# Motor_Driver.net
KiCad netlist of a schematic drawn in Altium Designer
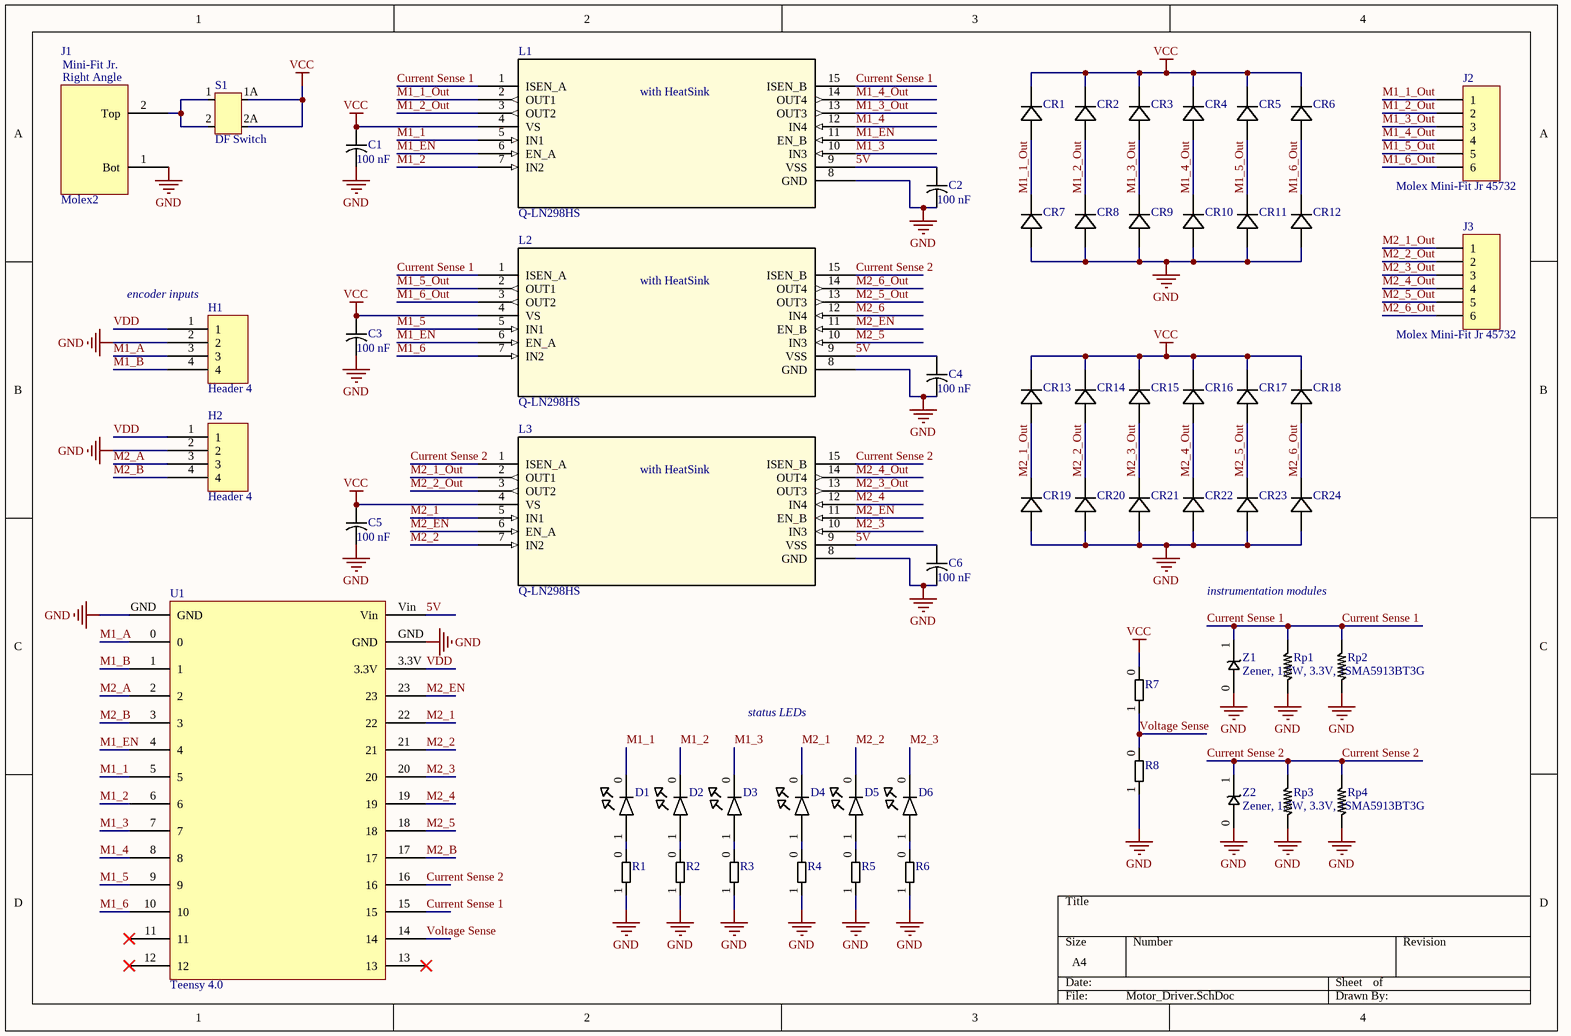
[diagram p0: Motor_Driver.SchDoc]

(export (version "E")
  (design (tool "Eeschema 10.0.6"))
  (components
    (comp (ref "C1")
      (value "100 nF")
      (footprint "CC0805N-M")
      (description "No Description Available")
      (fields
        (field (name "MANUFACTURER_PART_NUMBER") "C0805C104M5RACTU")
        (field (name "COPYRIGHT") "Copyright (C) 2018 Accelerated Designs. All rights reserved")
      )
      (libsource (lib "Motor_Driver") (part "C0805C104M5RACTU"))
    )
    (comp (ref "C2")
      (value "100 nF")
      (footprint "CC0805N-M")
      (description "No Description Available")
      (fields
        (field (name "MANUFACTURER_PART_NUMBER") "C0805C104M5RACTU")
        (field (name "COPYRIGHT") "Copyright (C) 2018 Accelerated Designs. All rights reserved")
      )
      (libsource (lib "Motor_Driver") (part "C0805C104M5RACTU"))
    )
    (comp (ref "C3")
      (value "100 nF")
      (footprint "CC0805N-M")
      (description "No Description Available")
      (fields
        (field (name "MANUFACTURER_PART_NUMBER") "C0805C104M5RACTU")
        (field (name "COPYRIGHT") "Copyright (C) 2018 Accelerated Designs. All rights reserved")
      )
      (libsource (lib "Motor_Driver") (part "C0805C104M5RACTU"))
    )
    (comp (ref "C4")
      (value "100 nF")
      (footprint "CC0805N-M")
      (description "No Description Available")
      (fields
        (field (name "MANUFACTURER_PART_NUMBER") "C0805C104M5RACTU")
        (field (name "COPYRIGHT") "Copyright (C) 2018 Accelerated Designs. All rights reserved")
      )
      (libsource (lib "Motor_Driver") (part "C0805C104M5RACTU"))
    )
    (comp (ref "C5")
      (value "100 nF")
      (footprint "CC0805N-M")
      (description "No Description Available")
      (fields
        (field (name "MANUFACTURER_PART_NUMBER") "C0805C104M5RACTU")
        (field (name "COPYRIGHT") "Copyright (C) 2018 Accelerated Designs. All rights reserved")
      )
      (libsource (lib "Motor_Driver") (part "C0805C104M5RACTU"))
    )
    (comp (ref "C6")
      (value "100 nF")
      (footprint "CC0805N-M")
      (description "No Description Available")
      (fields
        (field (name "MANUFACTURER_PART_NUMBER") "C0805C104M5RACTU")
        (field (name "COPYRIGHT") "Copyright (C) 2018 Accelerated Designs. All rights reserved")
      )
      (libsource (lib "Motor_Driver") (part "C0805C104M5RACTU"))
    )
    (comp (ref "CR1")
      (value "Part Number: SD1206S040S2R0")
      (footprint "SD1206")
      (fields
        (field (name "MANUFACTURER_PART_NUMBER") "SD1206S040S2R0")
        (field (name "COPYRIGHT") "Copyright (C) 2018 Accelerated Designs. All rights reserved")
      )
      (libsource (lib "Motor_Driver") (part "SD1206S040S2R0"))
    )
    (comp (ref "CR2")
      (value "Part Number: SD1206S040S2R0")
      (footprint "SD1206")
      (fields
        (field (name "MANUFACTURER_PART_NUMBER") "SD1206S040S2R0")
        (field (name "COPYRIGHT") "Copyright (C) 2018 Accelerated Designs. All rights reserved")
      )
      (libsource (lib "Motor_Driver") (part "SD1206S040S2R0"))
    )
    (comp (ref "CR3")
      (value "Part Number: SD1206S040S2R0")
      (footprint "SD1206")
      (fields
        (field (name "MANUFACTURER_PART_NUMBER") "SD1206S040S2R0")
        (field (name "COPYRIGHT") "Copyright (C) 2018 Accelerated Designs. All rights reserved")
      )
      (libsource (lib "Motor_Driver") (part "SD1206S040S2R0"))
    )
    (comp (ref "CR4")
      (value "Part Number: SD1206S040S2R0")
      (footprint "SD1206")
      (fields
        (field (name "MANUFACTURER_PART_NUMBER") "SD1206S040S2R0")
        (field (name "COPYRIGHT") "Copyright (C) 2018 Accelerated Designs. All rights reserved")
      )
      (libsource (lib "Motor_Driver") (part "SD1206S040S2R0"))
    )
    (comp (ref "CR5")
      (value "Part Number: SD1206S040S2R0")
      (footprint "SD1206")
      (fields
        (field (name "MANUFACTURER_PART_NUMBER") "SD1206S040S2R0")
        (field (name "COPYRIGHT") "Copyright (C) 2018 Accelerated Designs. All rights reserved")
      )
      (libsource (lib "Motor_Driver") (part "SD1206S040S2R0"))
    )
    (comp (ref "CR6")
      (value "Part Number: SD1206S040S2R0")
      (footprint "SD1206")
      (fields
        (field (name "MANUFACTURER_PART_NUMBER") "SD1206S040S2R0")
        (field (name "COPYRIGHT") "Copyright (C) 2018 Accelerated Designs. All rights reserved")
      )
      (libsource (lib "Motor_Driver") (part "SD1206S040S2R0"))
    )
    (comp (ref "CR7")
      (value "Part Number: SD1206S040S2R0")
      (footprint "SD1206")
      (fields
        (field (name "MANUFACTURER_PART_NUMBER") "SD1206S040S2R0")
        (field (name "COPYRIGHT") "Copyright (C) 2018 Accelerated Designs. All rights reserved")
      )
      (libsource (lib "Motor_Driver") (part "SD1206S040S2R0"))
    )
    (comp (ref "CR8")
      (value "Part Number: SD1206S040S2R0")
      (footprint "SD1206")
      (fields
        (field (name "MANUFACTURER_PART_NUMBER") "SD1206S040S2R0")
        (field (name "COPYRIGHT") "Copyright (C) 2018 Accelerated Designs. All rights reserved")
      )
      (libsource (lib "Motor_Driver") (part "SD1206S040S2R0"))
    )
    (comp (ref "CR9")
      (value "Part Number: SD1206S040S2R0")
      (footprint "SD1206")
      (fields
        (field (name "MANUFACTURER_PART_NUMBER") "SD1206S040S2R0")
        (field (name "COPYRIGHT") "Copyright (C) 2018 Accelerated Designs. All rights reserved")
      )
      (libsource (lib "Motor_Driver") (part "SD1206S040S2R0"))
    )
    (comp (ref "CR10")
      (value "Part Number: SD1206S040S2R0")
      (footprint "SD1206")
      (fields
        (field (name "MANUFACTURER_PART_NUMBER") "SD1206S040S2R0")
        (field (name "COPYRIGHT") "Copyright (C) 2018 Accelerated Designs. All rights reserved")
      )
      (libsource (lib "Motor_Driver") (part "SD1206S040S2R0"))
    )
    (comp (ref "CR11")
      (value "Part Number: SD1206S040S2R0")
      (footprint "SD1206")
      (fields
        (field (name "MANUFACTURER_PART_NUMBER") "SD1206S040S2R0")
        (field (name "COPYRIGHT") "Copyright (C) 2018 Accelerated Designs. All rights reserved")
      )
      (libsource (lib "Motor_Driver") (part "SD1206S040S2R0"))
    )
    (comp (ref "CR12")
      (value "Part Number: SD1206S040S2R0")
      (footprint "SD1206")
      (fields
        (field (name "MANUFACTURER_PART_NUMBER") "SD1206S040S2R0")
        (field (name "COPYRIGHT") "Copyright (C) 2018 Accelerated Designs. All rights reserved")
      )
      (libsource (lib "Motor_Driver") (part "SD1206S040S2R0"))
    )
    (comp (ref "CR13")
      (value "Part Number: SD1206S040S2R0")
      (footprint "SD1206")
      (fields
        (field (name "MANUFACTURER_PART_NUMBER") "SD1206S040S2R0")
        (field (name "COPYRIGHT") "Copyright (C) 2018 Accelerated Designs. All rights reserved")
      )
      (libsource (lib "Motor_Driver") (part "SD1206S040S2R0"))
    )
    (comp (ref "CR14")
      (value "Part Number: SD1206S040S2R0")
      (footprint "SD1206")
      (fields
        (field (name "MANUFACTURER_PART_NUMBER") "SD1206S040S2R0")
        (field (name "COPYRIGHT") "Copyright (C) 2018 Accelerated Designs. All rights reserved")
      )
      (libsource (lib "Motor_Driver") (part "SD1206S040S2R0"))
    )
    (comp (ref "CR15")
      (value "Part Number: SD1206S040S2R0")
      (footprint "SD1206")
      (fields
        (field (name "MANUFACTURER_PART_NUMBER") "SD1206S040S2R0")
        (field (name "COPYRIGHT") "Copyright (C) 2018 Accelerated Designs. All rights reserved")
      )
      (libsource (lib "Motor_Driver") (part "SD1206S040S2R0"))
    )
    (comp (ref "CR16")
      (value "Part Number: SD1206S040S2R0")
      (footprint "SD1206")
      (fields
        (field (name "MANUFACTURER_PART_NUMBER") "SD1206S040S2R0")
        (field (name "COPYRIGHT") "Copyright (C) 2018 Accelerated Designs. All rights reserved")
      )
      (libsource (lib "Motor_Driver") (part "SD1206S040S2R0"))
    )
    (comp (ref "CR17")
      (value "Part Number: SD1206S040S2R0")
      (footprint "SD1206")
      (fields
        (field (name "MANUFACTURER_PART_NUMBER") "SD1206S040S2R0")
        (field (name "COPYRIGHT") "Copyright (C) 2018 Accelerated Designs. All rights reserved")
      )
      (libsource (lib "Motor_Driver") (part "SD1206S040S2R0"))
    )
    (comp (ref "CR18")
      (value "Part Number: SD1206S040S2R0")
      (footprint "SD1206")
      (fields
        (field (name "MANUFACTURER_PART_NUMBER") "SD1206S040S2R0")
        (field (name "COPYRIGHT") "Copyright (C) 2018 Accelerated Designs. All rights reserved")
      )
      (libsource (lib "Motor_Driver") (part "SD1206S040S2R0"))
    )
    (comp (ref "CR19")
      (value "Part Number: SD1206S040S2R0")
      (footprint "SD1206")
      (fields
        (field (name "MANUFACTURER_PART_NUMBER") "SD1206S040S2R0")
        (field (name "COPYRIGHT") "Copyright (C) 2018 Accelerated Designs. All rights reserved")
      )
      (libsource (lib "Motor_Driver") (part "SD1206S040S2R0"))
    )
    (comp (ref "CR20")
      (value "Part Number: SD1206S040S2R0")
      (footprint "SD1206")
      (fields
        (field (name "MANUFACTURER_PART_NUMBER") "SD1206S040S2R0")
        (field (name "COPYRIGHT") "Copyright (C) 2018 Accelerated Designs. All rights reserved")
      )
      (libsource (lib "Motor_Driver") (part "SD1206S040S2R0"))
    )
    (comp (ref "CR21")
      (value "Part Number: SD1206S040S2R0")
      (footprint "SD1206")
      (fields
        (field (name "MANUFACTURER_PART_NUMBER") "SD1206S040S2R0")
        (field (name "COPYRIGHT") "Copyright (C) 2018 Accelerated Designs. All rights reserved")
      )
      (libsource (lib "Motor_Driver") (part "SD1206S040S2R0"))
    )
    (comp (ref "CR22")
      (value "Part Number: SD1206S040S2R0")
      (footprint "SD1206")
      (fields
        (field (name "MANUFACTURER_PART_NUMBER") "SD1206S040S2R0")
        (field (name "COPYRIGHT") "Copyright (C) 2018 Accelerated Designs. All rights reserved")
      )
      (libsource (lib "Motor_Driver") (part "SD1206S040S2R0"))
    )
    (comp (ref "CR23")
      (value "Part Number: SD1206S040S2R0")
      (footprint "SD1206")
      (fields
        (field (name "MANUFACTURER_PART_NUMBER") "SD1206S040S2R0")
        (field (name "COPYRIGHT") "Copyright (C) 2018 Accelerated Designs. All rights reserved")
      )
      (libsource (lib "Motor_Driver") (part "SD1206S040S2R0"))
    )
    (comp (ref "CR24")
      (value "Part Number: SD1206S040S2R0")
      (footprint "SD1206")
      (fields
        (field (name "MANUFACTURER_PART_NUMBER") "SD1206S040S2R0")
        (field (name "COPYRIGHT") "Copyright (C) 2018 Accelerated Designs. All rights reserved")
      )
      (libsource (lib "Motor_Driver") (part "SD1206S040S2R0"))
    )
    (comp (ref "D1")
      (value "Test LED")
      (footprint "Test LED")
      (libsource (lib "Motor_Driver") (part "Test LED"))
    )
    (comp (ref "D2")
      (value "Test LED")
      (footprint "Test LED")
      (libsource (lib "Motor_Driver") (part "Test LED"))
    )
    (comp (ref "D3")
      (value "Test LED")
      (footprint "Test LED")
      (libsource (lib "Motor_Driver") (part "Test LED"))
    )
    (comp (ref "D4")
      (value "Test LED")
      (footprint "Test LED")
      (libsource (lib "Motor_Driver") (part "Test LED"))
    )
    (comp (ref "D5")
      (value "Test LED")
      (footprint "Test LED")
      (libsource (lib "Motor_Driver") (part "Test LED"))
    )
    (comp (ref "D6")
      (value "Test LED")
      (footprint "Test LED")
      (libsource (lib "Motor_Driver") (part "Test LED"))
    )
    (comp (ref "H1")
      (value "Header 4")
      (footprint "4 Header")
      (libsource (lib "Motor_Driver") (part "Header 4"))
    )
    (comp (ref "H2")
      (value "Header 4")
      (footprint "4 Header")
      (libsource (lib "Motor_Driver") (part "Header 4"))
    )
    (comp (ref "J1")
      (value "Molex2")
      (footprint "MOLEX MINI2")
      (libsource (lib "Motor_Driver") (part "Molex2"))
    )
    (comp (ref "J2")
      (value "Molex Mini-Fit Jr 45732")
      (footprint "Molex Mini-Fit Jr")
      (description "Molex CONN HEADER R/A 6POS 4.2MM")
      (libsource (lib "Motor_Driver") (part "Molex 0457320001"))
    )
    (comp (ref "J3")
      (value "Molex Mini-Fit Jr 45732")
      (footprint "Molex Mini-Fit Jr")
      (description "Molex CONN HEADER R/A 6POS 4.2MM")
      (libsource (lib "Motor_Driver") (part "Molex 0457320001"))
    )
    (comp (ref "L1")
      (value "Q-LN298HS")
      (footprint "Multiwatt15_V_ELEC391HS")
      (description "LN298 - IC Bridge Driver Par 15Multiwatt")
      (fields
        (field (name "MANUFACTURER_PART_NUMBER") "L298N")
        (field (name "COPYRIGHT") "Copyright (C) 2015 Accelerated Designs. All rights reserved")
      )
      (libsource (lib "Additional Parts 391") (part "Q-LN298HS"))
    )
    (comp (ref "L2")
      (value "Q-LN298HS")
      (footprint "Multiwatt15_V_ELEC391HS")
      (description "LN298 - IC Bridge Driver Par 15Multiwatt")
      (fields
        (field (name "MANUFACTURER_PART_NUMBER") "L298N")
        (field (name "COPYRIGHT") "Copyright (C) 2015 Accelerated Designs. All rights reserved")
      )
      (libsource (lib "Additional Parts 391") (part "Q-LN298HS"))
    )
    (comp (ref "L3")
      (value "Q-LN298HS")
      (footprint "Multiwatt15_V_ELEC391HS")
      (description "LN298 - IC Bridge Driver Par 15Multiwatt")
      (fields
        (field (name "MANUFACTURER_PART_NUMBER") "L298N")
        (field (name "COPYRIGHT") "Copyright (C) 2015 Accelerated Designs. All rights reserved")
      )
      (libsource (lib "Additional Parts 391") (part "Q-LN298HS"))
    )
    (comp (ref "R1") (value "StdRes") (footprint "StdRes") (libsource (lib "Motor_Driver") (part "StdRes")))
    (comp (ref "R2") (value "StdRes") (footprint "StdRes") (libsource (lib "Motor_Driver") (part "StdRes")))
    (comp (ref "R3") (value "StdRes") (footprint "StdRes") (libsource (lib "Motor_Driver") (part "StdRes")))
    (comp (ref "R4") (value "StdRes") (footprint "StdRes") (libsource (lib "Motor_Driver") (part "StdRes")))
    (comp (ref "R5") (value "StdRes") (footprint "StdRes") (libsource (lib "Motor_Driver") (part "StdRes")))
    (comp (ref "R6") (value "StdRes") (footprint "StdRes") (libsource (lib "Motor_Driver") (part "StdRes")))
    (comp (ref "R7") (value "StdRes") (footprint "StdRes") (libsource (lib "Motor_Driver") (part "StdRes")))
    (comp (ref "R8") (value "StdRes") (footprint "StdRes") (libsource (lib "Motor_Driver") (part "StdRes")))
    (comp (ref "Rp1")
      (value "SQP500 Power Resistor")
      (footprint "SQP500 Power Resistor")
      (libsource (lib "Motor_Driver") (part "SQP500 Power Resistor"))
    )
    (comp (ref "Rp2")
      (value "SQP500 Power Resistor")
      (footprint "SQP500 Power Resistor")
      (libsource (lib "Motor_Driver") (part "SQP500 Power Resistor"))
    )
    (comp (ref "Rp3")
      (value "SQP500 Power Resistor")
      (footprint "SQP500 Power Resistor")
      (libsource (lib "Motor_Driver") (part "SQP500 Power Resistor"))
    )
    (comp (ref "Rp4")
      (value "SQP500 Power Resistor")
      (footprint "SQP500 Power Resistor")
      (libsource (lib "Motor_Driver") (part "SQP500 Power Resistor"))
    )
    (comp (ref "S1")
      (value "DF Switch")
      (footprint "DF Switch")
      (libsource (lib "Motor_Driver") (part "DF Switch"))
    )
    (comp (ref "U1")
      (value "Teensy 4.0")
      (footprint "Teensy 4.0")
      (libsource (lib "Motor_Driver") (part "Teensy 4.0"))
    )
    (comp (ref "Z1")
      (value "Zener, 1.5W, 3.3V, 1SMA5913BT3G")
      (footprint "Zener, 1.5W, 3.3V, 1SMA5913BT3G")
      (libsource (lib "Motor_Driver") (part "Zener, 1.5W, 3.3V, 1SMA5913BT3G"))
    )
    (comp (ref "Z2")
      (value "Zener, 1.5W, 3.3V, 1SMA5913BT3G")
      (footprint "Zener, 1.5W, 3.3V, 1SMA5913BT3G")
      (libsource (lib "Motor_Driver") (part "Zener, 1.5W, 3.3V, 1SMA5913BT3G"))
    )
  )
  (nets
    (net (code "1") (name "/5V") (class "Default")
      (node (ref "C2") (pin "1") (pinfunction "1_1") (pintype "passive"))
      (node (ref "C4") (pin "1") (pinfunction "1_1") (pintype "passive"))
      (node (ref "C6") (pin "1") (pinfunction "1_1") (pintype "passive"))
      (node (ref "L1") (pin "9") (pinfunction "VSS_9") (pintype "power_in"))
      (node (ref "L2") (pin "9") (pinfunction "VSS_9") (pintype "power_in"))
      (node (ref "L3") (pin "9") (pinfunction "VSS_9") (pintype "power_in"))
      (node (ref "U1") (pin "Vin") (pinfunction "Vin_Vin") (pintype "passive"))
    )
    (net (code "2") (name "/Current Sense 1") (class "Default")
      (node (ref "L1") (pin "1") (pinfunction "ISEN_A_1") (pintype "passive"))
      (node (ref "L1") (pin "15") (pinfunction "ISEN_B_15") (pintype "passive"))
      (node (ref "L2") (pin "1") (pinfunction "ISEN_A_1") (pintype "passive"))
      (node (ref "Rp1") (pin "1") (pintype "passive"))
      (node (ref "Rp2") (pin "1") (pintype "passive"))
      (node (ref "U1") (pin "15") (pinfunction "15_15") (pintype "passive"))
      (node (ref "Z1") (pin "1") (pinfunction "1_1") (pintype "passive"))
    )
    (net (code "3") (name "/Current Sense 2") (class "Default")
      (node (ref "L2") (pin "15") (pinfunction "ISEN_B_15") (pintype "passive"))
      (node (ref "L3") (pin "1") (pinfunction "ISEN_A_1") (pintype "passive"))
      (node (ref "L3") (pin "15") (pinfunction "ISEN_B_15") (pintype "passive"))
      (node (ref "Rp3") (pin "1") (pintype "passive"))
      (node (ref "Rp4") (pin "1") (pintype "passive"))
      (node (ref "U1") (pin "16") (pinfunction "16_16") (pintype "passive"))
      (node (ref "Z2") (pin "1") (pinfunction "1_1") (pintype "passive"))
    )
    (net (code "4") (name "/M1_1") (class "Default")
      (node (ref "D1") (pin "0") (pinfunction "0_0") (pintype "passive"))
      (node (ref "L1") (pin "5") (pinfunction "IN1_5") (pintype "input"))
      (node (ref "U1") (pin "5") (pinfunction "5_5") (pintype "passive"))
    )
    (net (code "5") (name "/M1_1_Out") (class "Default")
      (node (ref "CR1") (pin "2") (pinfunction "2_2") (pintype "passive"))
      (node (ref "CR7") (pin "1") (pinfunction "1_1") (pintype "passive"))
      (node (ref "J2") (pin "1") (pinfunction "1_1") (pintype "power_in"))
      (node (ref "L1") (pin "2") (pinfunction "OUT1_2") (pintype "output"))
    )
    (net (code "6") (name "/M1_2") (class "Default")
      (node (ref "D2") (pin "0") (pinfunction "0_0") (pintype "passive"))
      (node (ref "L1") (pin "7") (pinfunction "IN2_7") (pintype "input"))
      (node (ref "U1") (pin "6") (pinfunction "6_6") (pintype "passive"))
    )
    (net (code "7") (name "/M1_2_Out") (class "Default")
      (node (ref "CR2") (pin "2") (pinfunction "2_2") (pintype "passive"))
      (node (ref "CR8") (pin "1") (pinfunction "1_1") (pintype "passive"))
      (node (ref "J2") (pin "2") (pinfunction "2_2") (pintype "power_in"))
      (node (ref "L1") (pin "3") (pinfunction "OUT2_3") (pintype "output"))
    )
    (net (code "8") (name "/M1_3") (class "Default")
      (node (ref "D3") (pin "0") (pinfunction "0_0") (pintype "passive"))
      (node (ref "L1") (pin "10") (pinfunction "IN3_10") (pintype "input"))
      (node (ref "U1") (pin "7") (pinfunction "7_7") (pintype "passive"))
    )
    (net (code "9") (name "/M1_3_Out") (class "Default")
      (node (ref "CR3") (pin "2") (pinfunction "2_2") (pintype "passive"))
      (node (ref "CR9") (pin "1") (pinfunction "1_1") (pintype "passive"))
      (node (ref "J2") (pin "3") (pinfunction "3_3") (pintype "power_in"))
      (node (ref "L1") (pin "13") (pinfunction "OUT3_13") (pintype "output"))
    )
    (net (code "10") (name "/M1_4") (class "Default")
      (node (ref "L1") (pin "12") (pinfunction "IN4_12") (pintype "input"))
      (node (ref "U1") (pin "8") (pinfunction "8_8") (pintype "passive"))
    )
    (net (code "11") (name "/M1_4_Out") (class "Default")
      (node (ref "CR10") (pin "1") (pinfunction "1_1") (pintype "passive"))
      (node (ref "CR4") (pin "2") (pinfunction "2_2") (pintype "passive"))
      (node (ref "J2") (pin "4") (pinfunction "4_4") (pintype "power_in"))
      (node (ref "L1") (pin "14") (pinfunction "OUT4_14") (pintype "output"))
    )
    (net (code "12") (name "/M1_5") (class "Default")
      (node (ref "L2") (pin "5") (pinfunction "IN1_5") (pintype "input"))
      (node (ref "U1") (pin "9") (pinfunction "9_9") (pintype "passive"))
    )
    (net (code "13") (name "/M1_5_Out") (class "Default")
      (node (ref "CR11") (pin "1") (pinfunction "1_1") (pintype "passive"))
      (node (ref "CR5") (pin "2") (pinfunction "2_2") (pintype "passive"))
      (node (ref "J2") (pin "5") (pinfunction "5_5") (pintype "power_in"))
      (node (ref "L2") (pin "2") (pinfunction "OUT1_2") (pintype "output"))
    )
    (net (code "14") (name "/M1_6") (class "Default")
      (node (ref "L2") (pin "7") (pinfunction "IN2_7") (pintype "input"))
      (node (ref "U1") (pin "10") (pinfunction "10_10") (pintype "passive"))
    )
    (net (code "15") (name "/M1_6_Out") (class "Default")
      (node (ref "CR12") (pin "1") (pinfunction "1_1") (pintype "passive"))
      (node (ref "CR6") (pin "2") (pinfunction "2_2") (pintype "passive"))
      (node (ref "J2") (pin "6") (pinfunction "6_6") (pintype "power_in"))
      (node (ref "L2") (pin "3") (pinfunction "OUT2_3") (pintype "output"))
    )
    (net (code "16") (name "/M1_A") (class "Default")
      (node (ref "H1") (pin "3") (pinfunction "3_3") (pintype "passive"))
      (node (ref "U1") (pin "0") (pinfunction "0_0") (pintype "passive"))
    )
    (net (code "17") (name "/M1_B") (class "Default")
      (node (ref "H1") (pin "4") (pinfunction "4_4") (pintype "passive"))
      (node (ref "U1") (pin "1") (pinfunction "1_1") (pintype "passive"))
    )
    (net (code "18") (name "/M1_EN") (class "Default")
      (node (ref "L1") (pin "11") (pinfunction "EN_B_11") (pintype "input"))
      (node (ref "L1") (pin "6") (pinfunction "EN_A_6") (pintype "input"))
      (node (ref "L2") (pin "6") (pinfunction "EN_A_6") (pintype "input"))
      (node (ref "U1") (pin "4") (pinfunction "4_4") (pintype "passive"))
    )
    (net (code "19") (name "/M2_1") (class "Default")
      (node (ref "D4") (pin "0") (pinfunction "0_0") (pintype "passive"))
      (node (ref "L3") (pin "5") (pinfunction "IN1_5") (pintype "input"))
      (node (ref "U1") (pin "22") (pinfunction "22_22") (pintype "passive"))
    )
    (net (code "20") (name "/M2_1_Out") (class "Default")
      (node (ref "CR13") (pin "2") (pinfunction "2_2") (pintype "passive"))
      (node (ref "CR19") (pin "1") (pinfunction "1_1") (pintype "passive"))
      (node (ref "J3") (pin "1") (pinfunction "1_1") (pintype "power_in"))
      (node (ref "L3") (pin "2") (pinfunction "OUT1_2") (pintype "output"))
    )
    (net (code "21") (name "/M2_2") (class "Default")
      (node (ref "D5") (pin "0") (pinfunction "0_0") (pintype "passive"))
      (node (ref "L3") (pin "7") (pinfunction "IN2_7") (pintype "input"))
      (node (ref "U1") (pin "21") (pinfunction "21_21") (pintype "passive"))
    )
    (net (code "22") (name "/M2_2_Out") (class "Default")
      (node (ref "CR14") (pin "2") (pinfunction "2_2") (pintype "passive"))
      (node (ref "CR20") (pin "1") (pinfunction "1_1") (pintype "passive"))
      (node (ref "J3") (pin "2") (pinfunction "2_2") (pintype "power_in"))
      (node (ref "L3") (pin "3") (pinfunction "OUT2_3") (pintype "output"))
    )
    (net (code "23") (name "/M2_3") (class "Default")
      (node (ref "D6") (pin "0") (pinfunction "0_0") (pintype "passive"))
      (node (ref "L3") (pin "10") (pinfunction "IN3_10") (pintype "input"))
      (node (ref "U1") (pin "20") (pinfunction "20_20") (pintype "passive"))
    )
    (net (code "24") (name "/M2_3_Out") (class "Default")
      (node (ref "CR15") (pin "2") (pinfunction "2_2") (pintype "passive"))
      (node (ref "CR21") (pin "1") (pinfunction "1_1") (pintype "passive"))
      (node (ref "J3") (pin "3") (pinfunction "3_3") (pintype "power_in"))
      (node (ref "L3") (pin "13") (pinfunction "OUT3_13") (pintype "output"))
    )
    (net (code "25") (name "/M2_4") (class "Default")
      (node (ref "L3") (pin "12") (pinfunction "IN4_12") (pintype "input"))
      (node (ref "U1") (pin "19") (pinfunction "19_19") (pintype "passive"))
    )
    (net (code "26") (name "/M2_4_Out") (class "Default")
      (node (ref "CR16") (pin "2") (pinfunction "2_2") (pintype "passive"))
      (node (ref "CR22") (pin "1") (pinfunction "1_1") (pintype "passive"))
      (node (ref "J3") (pin "4") (pinfunction "4_4") (pintype "power_in"))
      (node (ref "L3") (pin "14") (pinfunction "OUT4_14") (pintype "output"))
    )
    (net (code "27") (name "/M2_5") (class "Default")
      (node (ref "L2") (pin "10") (pinfunction "IN3_10") (pintype "input"))
      (node (ref "U1") (pin "18") (pinfunction "18_18") (pintype "passive"))
    )
    (net (code "28") (name "/M2_5_Out") (class "Default")
      (node (ref "CR17") (pin "2") (pinfunction "2_2") (pintype "passive"))
      (node (ref "CR23") (pin "1") (pinfunction "1_1") (pintype "passive"))
      (node (ref "J3") (pin "5") (pinfunction "5_5") (pintype "power_in"))
      (node (ref "L2") (pin "13") (pinfunction "OUT3_13") (pintype "output"))
    )
    (net (code "29") (name "/M2_6") (class "Default")
      (node (ref "L2") (pin "12") (pinfunction "IN4_12") (pintype "input"))
    )
    (net (code "30") (name "/M2_6_Out") (class "Default")
      (node (ref "CR18") (pin "2") (pinfunction "2_2") (pintype "passive"))
      (node (ref "CR24") (pin "1") (pinfunction "1_1") (pintype "passive"))
      (node (ref "J3") (pin "6") (pinfunction "6_6") (pintype "power_in"))
      (node (ref "L2") (pin "14") (pinfunction "OUT4_14") (pintype "output"))
    )
    (net (code "31") (name "/M2_A") (class "Default")
      (node (ref "H2") (pin "3") (pinfunction "3_3") (pintype "passive"))
      (node (ref "U1") (pin "2") (pinfunction "2_2") (pintype "passive"))
    )
    (net (code "32") (name "/M2_B") (class "Default")
      (node (ref "H2") (pin "4") (pinfunction "4_4") (pintype "passive"))
      (node (ref "U1") (pin "17") (pinfunction "17_17") (pintype "passive"))
      (node (ref "U1") (pin "3") (pinfunction "3_3") (pintype "passive"))
    )
    (net (code "33") (name "/M2_EN") (class "Default")
      (node (ref "L2") (pin "11") (pinfunction "EN_B_11") (pintype "input"))
      (node (ref "L3") (pin "11") (pinfunction "EN_B_11") (pintype "input"))
      (node (ref "L3") (pin "6") (pinfunction "EN_A_6") (pintype "input"))
      (node (ref "U1") (pin "23") (pinfunction "23_23") (pintype "passive"))
    )
    (net (code "34") (name "/VDD") (class "Default")
      (node (ref "H1") (pin "1") (pinfunction "1_1") (pintype "passive"))
      (node (ref "H2") (pin "1") (pinfunction "1_1") (pintype "passive"))
      (node (ref "U1") (pin "3.3V") (pinfunction "3.3V_3.3V") (pintype "passive"))
    )
    (net (code "35") (name "/Voltage Sense") (class "Default")
      (node (ref "R7") (pin "1") (pinfunction "1_1") (pintype "passive"))
      (node (ref "R8") (pin "0") (pinfunction "0_0") (pintype "passive"))
      (node (ref "U1") (pin "14") (pinfunction "14_14") (pintype "passive"))
    )
    (net (code "36") (name "GND") (class "Default")
      (node (ref "C1") (pin "2") (pinfunction "2_2") (pintype "passive"))
      (node (ref "C2") (pin "2") (pinfunction "2_2") (pintype "passive"))
      (node (ref "C3") (pin "2") (pinfunction "2_2") (pintype "passive"))
      (node (ref "C4") (pin "2") (pinfunction "2_2") (pintype "passive"))
      (node (ref "C5") (pin "2") (pinfunction "2_2") (pintype "passive"))
      (node (ref "C6") (pin "2") (pinfunction "2_2") (pintype "passive"))
      (node (ref "CR10") (pin "2") (pinfunction "2_2") (pintype "passive"))
      (node (ref "CR11") (pin "2") (pinfunction "2_2") (pintype "passive"))
      (node (ref "CR12") (pin "2") (pinfunction "2_2") (pintype "passive"))
      (node (ref "CR19") (pin "2") (pinfunction "2_2") (pintype "passive"))
      (node (ref "CR20") (pin "2") (pinfunction "2_2") (pintype "passive"))
      (node (ref "CR21") (pin "2") (pinfunction "2_2") (pintype "passive"))
      (node (ref "CR22") (pin "2") (pinfunction "2_2") (pintype "passive"))
      (node (ref "CR23") (pin "2") (pinfunction "2_2") (pintype "passive"))
      (node (ref "CR24") (pin "2") (pinfunction "2_2") (pintype "passive"))
      (node (ref "CR7") (pin "2") (pinfunction "2_2") (pintype "passive"))
      (node (ref "CR8") (pin "2") (pinfunction "2_2") (pintype "passive"))
      (node (ref "CR9") (pin "2") (pinfunction "2_2") (pintype "passive"))
      (node (ref "H1") (pin "2") (pinfunction "2_2") (pintype "passive"))
      (node (ref "H2") (pin "2") (pinfunction "2_2") (pintype "passive"))
      (node (ref "J1") (pin "1") (pinfunction "Bot_1") (pintype "passive"))
      (node (ref "L1") (pin "8") (pinfunction "GND_8") (pintype "power_in"))
      (node (ref "L2") (pin "8") (pinfunction "GND_8") (pintype "power_in"))
      (node (ref "L3") (pin "8") (pinfunction "GND_8") (pintype "power_in"))
      (node (ref "R1") (pin "1") (pinfunction "1_1") (pintype "passive"))
      (node (ref "R2") (pin "1") (pinfunction "1_1") (pintype "passive"))
      (node (ref "R3") (pin "1") (pinfunction "1_1") (pintype "passive"))
      (node (ref "R4") (pin "1") (pinfunction "1_1") (pintype "passive"))
      (node (ref "R5") (pin "1") (pinfunction "1_1") (pintype "passive"))
      (node (ref "R6") (pin "1") (pinfunction "1_1") (pintype "passive"))
      (node (ref "R8") (pin "1") (pinfunction "1_1") (pintype "passive"))
      (node (ref "Rp1") (pin "0") (pintype "passive"))
      (node (ref "Rp2") (pin "0") (pintype "passive"))
      (node (ref "Rp3") (pin "0") (pintype "passive"))
      (node (ref "Rp4") (pin "0") (pintype "passive"))
      (node (ref "U1") (pin "GND") (pinfunction "GND_GND") (pintype "passive"))
      (node (ref "Z1") (pin "0") (pinfunction "0_0") (pintype "passive"))
      (node (ref "Z2") (pin "0") (pinfunction "0_0") (pintype "passive"))
    )
    (net (code "37") (name "Net-(D1-Pad1)") (class "Default")
      (node (ref "D1") (pin "1") (pinfunction "1_1") (pintype "passive"))
      (node (ref "R1") (pin "0") (pinfunction "0_0") (pintype "passive"))
    )
    (net (code "38") (name "Net-(D2-Pad1)") (class "Default")
      (node (ref "D2") (pin "1") (pinfunction "1_1") (pintype "passive"))
      (node (ref "R2") (pin "0") (pinfunction "0_0") (pintype "passive"))
    )
    (net (code "39") (name "Net-(D3-Pad1)") (class "Default")
      (node (ref "D3") (pin "1") (pinfunction "1_1") (pintype "passive"))
      (node (ref "R3") (pin "0") (pinfunction "0_0") (pintype "passive"))
    )
    (net (code "40") (name "Net-(D4-Pad1)") (class "Default")
      (node (ref "D4") (pin "1") (pinfunction "1_1") (pintype "passive"))
      (node (ref "R4") (pin "0") (pinfunction "0_0") (pintype "passive"))
    )
    (net (code "41") (name "Net-(D5-Pad1)") (class "Default")
      (node (ref "D5") (pin "1") (pinfunction "1_1") (pintype "passive"))
      (node (ref "R5") (pin "0") (pinfunction "0_0") (pintype "passive"))
    )
    (net (code "42") (name "Net-(D6-Pad1)") (class "Default")
      (node (ref "D6") (pin "1") (pinfunction "1_1") (pintype "passive"))
      (node (ref "R6") (pin "0") (pinfunction "0_0") (pintype "passive"))
    )
    (net (code "43") (name "Net-(J1-Top)") (class "Default")
      (node (ref "J1") (pin "2") (pinfunction "Top_2") (pintype "passive"))
      (node (ref "S1") (pin "1") (pinfunction "1_1") (pintype "passive"))
      (node (ref "S1") (pin "2") (pinfunction "0_2") (pintype "passive"))
    )
    (net (code "44") (name "VCC") (class "Default")
      (node (ref "C1") (pin "1") (pinfunction "1_1") (pintype "passive"))
      (node (ref "C3") (pin "1") (pinfunction "1_1") (pintype "passive"))
      (node (ref "C5") (pin "1") (pinfunction "1_1") (pintype "passive"))
      (node (ref "CR1") (pin "1") (pinfunction "1_1") (pintype "passive"))
      (node (ref "CR13") (pin "1") (pinfunction "1_1") (pintype "passive"))
      (node (ref "CR14") (pin "1") (pinfunction "1_1") (pintype "passive"))
      (node (ref "CR15") (pin "1") (pinfunction "1_1") (pintype "passive"))
      (node (ref "CR16") (pin "1") (pinfunction "1_1") (pintype "passive"))
      (node (ref "CR17") (pin "1") (pinfunction "1_1") (pintype "passive"))
      (node (ref "CR18") (pin "1") (pinfunction "1_1") (pintype "passive"))
      (node (ref "CR2") (pin "1") (pinfunction "1_1") (pintype "passive"))
      (node (ref "CR3") (pin "1") (pinfunction "1_1") (pintype "passive"))
      (node (ref "CR4") (pin "1") (pinfunction "1_1") (pintype "passive"))
      (node (ref "CR5") (pin "1") (pinfunction "1_1") (pintype "passive"))
      (node (ref "CR6") (pin "1") (pinfunction "1_1") (pintype "passive"))
      (node (ref "L1") (pin "4") (pinfunction "VS_4") (pintype "power_in"))
      (node (ref "L2") (pin "4") (pinfunction "VS_4") (pintype "power_in"))
      (node (ref "L3") (pin "4") (pinfunction "VS_4") (pintype "power_in"))
      (node (ref "R7") (pin "0") (pinfunction "0_0") (pintype "passive"))
      (node (ref "S1") (pin "1A") (pinfunction "0_1A") (pintype "passive"))
      (node (ref "S1") (pin "2A") (pinfunction "2A_2A") (pintype "passive"))
    )
    (net (code "45") (name "unconnected-(U1-Pad11)") (class "Default")
      (node (ref "U1") (pin "11") (pinfunction "11_11") (pintype "passive+no_connect"))
    )
    (net (code "46") (name "unconnected-(U1-Pad12)") (class "Default")
      (node (ref "U1") (pin "12") (pinfunction "12_12") (pintype "passive+no_connect"))
    )
    (net (code "47") (name "unconnected-(U1-Pad13)") (class "Default")
      (node (ref "U1") (pin "13") (pinfunction "13_13") (pintype "passive+no_connect"))
    )
  )
)
